# Sheet1.net
KiCad netlist of a schematic drawn in Altium Designer
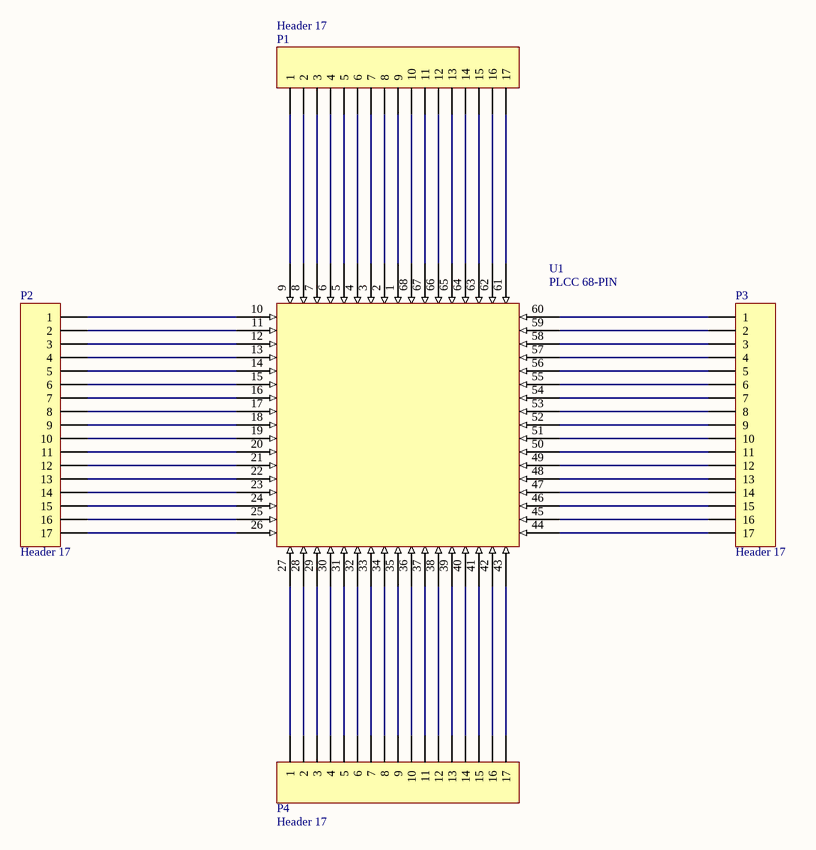
[diagram p0: Sheet1.SchDoc]

(export (version "E")
  (design (tool "Eeschema 10.0.6"))
  (components
    (comp (ref "P1")
      (value "Header 17")
      (footprint "HDR1X17")
      (description "Header, 17-Pin")
      (fields (field (name "PUBLISHER") "Altium Limited"))
      (libsource (lib "") (part "Header 17_3"))
    )
    (comp (ref "P2")
      (value "Header 17")
      (footprint "HDR1X17")
      (description "Header, 17-Pin")
      (fields (field (name "PUBLISHER") "Altium Limited"))
      (libsource (lib "Miscellaneous Connectors") (part "Header 17"))
    )
    (comp (ref "P3")
      (value "Header 17")
      (footprint "HDR1X17")
      (description "Header, 17-Pin")
      (fields (field (name "PUBLISHER") "Altium Limited"))
      (libsource (lib "") (part "Header 17_2"))
    )
    (comp (ref "P4")
      (value "Header 17")
      (footprint "HDR1X17")
      (description "Header, 17-Pin")
      (fields (field (name "PUBLISHER") "Altium Limited"))
      (libsource (lib "") (part "Header 17_1"))
    )
    (comp (ref "U1")
      (value "PLCC 68-PIN")
      (footprint "PcbLib1:PLCC68")
      (description "Custom IC")
      (libsource (lib "Schlib1") (part "PLCC 68-PIN"))
    )
  )
  (nets
    (net (code "1") (name "Net-(P1-Pad1)") (class "Default")
      (node (ref "P1") (pin "1") (pinfunction "1_1") (pintype "passive"))
      (node (ref "U1") (pin "9") (pintype "input"))
    )
    (net (code "2") (name "Net-(P1-Pad2)") (class "Default")
      (node (ref "P1") (pin "2") (pinfunction "2_2") (pintype "passive"))
      (node (ref "U1") (pin "8") (pintype "input"))
    )
    (net (code "3") (name "Net-(P1-Pad3)") (class "Default")
      (node (ref "P1") (pin "3") (pinfunction "3_3") (pintype "passive"))
      (node (ref "U1") (pin "7") (pintype "input"))
    )
    (net (code "4") (name "Net-(P1-Pad4)") (class "Default")
      (node (ref "P1") (pin "4") (pinfunction "4_4") (pintype "passive"))
      (node (ref "U1") (pin "6") (pintype "input"))
    )
    (net (code "5") (name "Net-(P1-Pad5)") (class "Default")
      (node (ref "P1") (pin "5") (pinfunction "5_5") (pintype "passive"))
      (node (ref "U1") (pin "5") (pintype "input"))
    )
    (net (code "6") (name "Net-(P1-Pad6)") (class "Default")
      (node (ref "P1") (pin "6") (pinfunction "6_6") (pintype "passive"))
      (node (ref "U1") (pin "4") (pintype "input"))
    )
    (net (code "7") (name "Net-(P1-Pad7)") (class "Default")
      (node (ref "P1") (pin "7") (pinfunction "7_7") (pintype "passive"))
      (node (ref "U1") (pin "3") (pintype "input"))
    )
    (net (code "8") (name "Net-(P1-Pad8)") (class "Default")
      (node (ref "P1") (pin "8") (pinfunction "8_8") (pintype "passive"))
      (node (ref "U1") (pin "2") (pintype "input"))
    )
    (net (code "9") (name "Net-(P1-Pad9)") (class "Default")
      (node (ref "P1") (pin "9") (pinfunction "9_9") (pintype "passive"))
      (node (ref "U1") (pin "1") (pintype "input"))
    )
    (net (code "10") (name "Net-(P1-Pad10)") (class "Default")
      (node (ref "P1") (pin "10") (pinfunction "10_10") (pintype "passive"))
      (node (ref "U1") (pin "68") (pintype "input"))
    )
    (net (code "11") (name "Net-(P1-Pad11)") (class "Default")
      (node (ref "P1") (pin "11") (pinfunction "11_11") (pintype "passive"))
      (node (ref "U1") (pin "67") (pintype "input"))
    )
    (net (code "12") (name "Net-(P1-Pad12)") (class "Default")
      (node (ref "P1") (pin "12") (pinfunction "12_12") (pintype "passive"))
      (node (ref "U1") (pin "66") (pintype "input"))
    )
    (net (code "13") (name "Net-(P1-Pad13)") (class "Default")
      (node (ref "P1") (pin "13") (pinfunction "13_13") (pintype "passive"))
      (node (ref "U1") (pin "65") (pintype "input"))
    )
    (net (code "14") (name "Net-(P1-Pad14)") (class "Default")
      (node (ref "P1") (pin "14") (pinfunction "14_14") (pintype "passive"))
      (node (ref "U1") (pin "64") (pintype "input"))
    )
    (net (code "15") (name "Net-(P1-Pad15)") (class "Default")
      (node (ref "P1") (pin "15") (pinfunction "15_15") (pintype "passive"))
      (node (ref "U1") (pin "63") (pintype "input"))
    )
    (net (code "16") (name "Net-(P1-Pad16)") (class "Default")
      (node (ref "P1") (pin "16") (pinfunction "16_16") (pintype "passive"))
      (node (ref "U1") (pin "62") (pintype "input"))
    )
    (net (code "17") (name "Net-(P1-Pad17)") (class "Default")
      (node (ref "P1") (pin "17") (pinfunction "17_17") (pintype "passive"))
      (node (ref "U1") (pin "61") (pintype "input"))
    )
    (net (code "18") (name "Net-(P2-Pad1)") (class "Default")
      (node (ref "P2") (pin "1") (pinfunction "1_1") (pintype "passive"))
      (node (ref "U1") (pin "10") (pintype "input"))
    )
    (net (code "19") (name "Net-(P2-Pad2)") (class "Default")
      (node (ref "P2") (pin "2") (pinfunction "2_2") (pintype "passive"))
      (node (ref "U1") (pin "11") (pintype "input"))
    )
    (net (code "20") (name "Net-(P2-Pad3)") (class "Default")
      (node (ref "P2") (pin "3") (pinfunction "3_3") (pintype "passive"))
      (node (ref "U1") (pin "12") (pintype "input"))
    )
    (net (code "21") (name "Net-(P2-Pad4)") (class "Default")
      (node (ref "P2") (pin "4") (pinfunction "4_4") (pintype "passive"))
      (node (ref "U1") (pin "13") (pintype "input"))
    )
    (net (code "22") (name "Net-(P2-Pad5)") (class "Default")
      (node (ref "P2") (pin "5") (pinfunction "5_5") (pintype "passive"))
      (node (ref "U1") (pin "14") (pintype "input"))
    )
    (net (code "23") (name "Net-(P2-Pad6)") (class "Default")
      (node (ref "P2") (pin "6") (pinfunction "6_6") (pintype "passive"))
      (node (ref "U1") (pin "15") (pintype "input"))
    )
    (net (code "24") (name "Net-(P2-Pad7)") (class "Default")
      (node (ref "P2") (pin "7") (pinfunction "7_7") (pintype "passive"))
      (node (ref "U1") (pin "16") (pintype "input"))
    )
    (net (code "25") (name "Net-(P2-Pad8)") (class "Default")
      (node (ref "P2") (pin "8") (pinfunction "8_8") (pintype "passive"))
      (node (ref "U1") (pin "17") (pintype "input"))
    )
    (net (code "26") (name "Net-(P2-Pad9)") (class "Default")
      (node (ref "P2") (pin "9") (pinfunction "9_9") (pintype "passive"))
      (node (ref "U1") (pin "18") (pintype "input"))
    )
    (net (code "27") (name "Net-(P2-Pad10)") (class "Default")
      (node (ref "P2") (pin "10") (pinfunction "10_10") (pintype "passive"))
      (node (ref "U1") (pin "19") (pintype "input"))
    )
    (net (code "28") (name "Net-(P2-Pad11)") (class "Default")
      (node (ref "P2") (pin "11") (pinfunction "11_11") (pintype "passive"))
      (node (ref "U1") (pin "20") (pintype "input"))
    )
    (net (code "29") (name "Net-(P2-Pad12)") (class "Default")
      (node (ref "P2") (pin "12") (pinfunction "12_12") (pintype "passive"))
      (node (ref "U1") (pin "21") (pintype "input"))
    )
    (net (code "30") (name "Net-(P2-Pad13)") (class "Default")
      (node (ref "P2") (pin "13") (pinfunction "13_13") (pintype "passive"))
      (node (ref "U1") (pin "22") (pintype "input"))
    )
    (net (code "31") (name "Net-(P2-Pad14)") (class "Default")
      (node (ref "P2") (pin "14") (pinfunction "14_14") (pintype "passive"))
      (node (ref "U1") (pin "23") (pintype "input"))
    )
    (net (code "32") (name "Net-(P2-Pad15)") (class "Default")
      (node (ref "P2") (pin "15") (pinfunction "15_15") (pintype "passive"))
      (node (ref "U1") (pin "24") (pintype "input"))
    )
    (net (code "33") (name "Net-(P2-Pad16)") (class "Default")
      (node (ref "P2") (pin "16") (pinfunction "16_16") (pintype "passive"))
      (node (ref "U1") (pin "25") (pintype "input"))
    )
    (net (code "34") (name "Net-(P2-Pad17)") (class "Default")
      (node (ref "P2") (pin "17") (pinfunction "17_17") (pintype "passive"))
      (node (ref "U1") (pin "26") (pintype "input"))
    )
    (net (code "35") (name "Net-(P3-Pad1)") (class "Default")
      (node (ref "P3") (pin "1") (pinfunction "1_1") (pintype "passive"))
      (node (ref "U1") (pin "60") (pintype "input"))
    )
    (net (code "36") (name "Net-(P3-Pad2)") (class "Default")
      (node (ref "P3") (pin "2") (pinfunction "2_2") (pintype "passive"))
      (node (ref "U1") (pin "59") (pintype "input"))
    )
    (net (code "37") (name "Net-(P3-Pad3)") (class "Default")
      (node (ref "P3") (pin "3") (pinfunction "3_3") (pintype "passive"))
      (node (ref "U1") (pin "58") (pintype "input"))
    )
    (net (code "38") (name "Net-(P3-Pad4)") (class "Default")
      (node (ref "P3") (pin "4") (pinfunction "4_4") (pintype "passive"))
      (node (ref "U1") (pin "57") (pintype "input"))
    )
    (net (code "39") (name "Net-(P3-Pad5)") (class "Default")
      (node (ref "P3") (pin "5") (pinfunction "5_5") (pintype "passive"))
      (node (ref "U1") (pin "56") (pintype "input"))
    )
    (net (code "40") (name "Net-(P3-Pad6)") (class "Default")
      (node (ref "P3") (pin "6") (pinfunction "6_6") (pintype "passive"))
      (node (ref "U1") (pin "55") (pintype "input"))
    )
    (net (code "41") (name "Net-(P3-Pad7)") (class "Default")
      (node (ref "P3") (pin "7") (pinfunction "7_7") (pintype "passive"))
      (node (ref "U1") (pin "54") (pintype "input"))
    )
    (net (code "42") (name "Net-(P3-Pad8)") (class "Default")
      (node (ref "P3") (pin "8") (pinfunction "8_8") (pintype "passive"))
      (node (ref "U1") (pin "53") (pintype "input"))
    )
    (net (code "43") (name "Net-(P3-Pad9)") (class "Default")
      (node (ref "P3") (pin "9") (pinfunction "9_9") (pintype "passive"))
      (node (ref "U1") (pin "52") (pintype "input"))
    )
    (net (code "44") (name "Net-(P3-Pad10)") (class "Default")
      (node (ref "P3") (pin "10") (pinfunction "10_10") (pintype "passive"))
      (node (ref "U1") (pin "51") (pintype "input"))
    )
    (net (code "45") (name "Net-(P3-Pad11)") (class "Default")
      (node (ref "P3") (pin "11") (pinfunction "11_11") (pintype "passive"))
      (node (ref "U1") (pin "50") (pintype "input"))
    )
    (net (code "46") (name "Net-(P3-Pad12)") (class "Default")
      (node (ref "P3") (pin "12") (pinfunction "12_12") (pintype "passive"))
      (node (ref "U1") (pin "49") (pintype "input"))
    )
    (net (code "47") (name "Net-(P3-Pad13)") (class "Default")
      (node (ref "P3") (pin "13") (pinfunction "13_13") (pintype "passive"))
      (node (ref "U1") (pin "48") (pintype "input"))
    )
    (net (code "48") (name "Net-(P3-Pad14)") (class "Default")
      (node (ref "P3") (pin "14") (pinfunction "14_14") (pintype "passive"))
      (node (ref "U1") (pin "47") (pintype "input"))
    )
    (net (code "49") (name "Net-(P3-Pad15)") (class "Default")
      (node (ref "P3") (pin "15") (pinfunction "15_15") (pintype "passive"))
      (node (ref "U1") (pin "46") (pintype "input"))
    )
    (net (code "50") (name "Net-(P3-Pad16)") (class "Default")
      (node (ref "P3") (pin "16") (pinfunction "16_16") (pintype "passive"))
      (node (ref "U1") (pin "45") (pintype "input"))
    )
    (net (code "51") (name "Net-(P3-Pad17)") (class "Default")
      (node (ref "P3") (pin "17") (pinfunction "17_17") (pintype "passive"))
      (node (ref "U1") (pin "44") (pintype "input"))
    )
    (net (code "52") (name "Net-(P4-Pad1)") (class "Default")
      (node (ref "P4") (pin "1") (pinfunction "1_1") (pintype "passive"))
      (node (ref "U1") (pin "27") (pintype "input"))
    )
    (net (code "53") (name "Net-(P4-Pad2)") (class "Default")
      (node (ref "P4") (pin "2") (pinfunction "2_2") (pintype "passive"))
      (node (ref "U1") (pin "28") (pintype "input"))
    )
    (net (code "54") (name "Net-(P4-Pad3)") (class "Default")
      (node (ref "P4") (pin "3") (pinfunction "3_3") (pintype "passive"))
      (node (ref "U1") (pin "29") (pintype "input"))
    )
    (net (code "55") (name "Net-(P4-Pad4)") (class "Default")
      (node (ref "P4") (pin "4") (pinfunction "4_4") (pintype "passive"))
      (node (ref "U1") (pin "30") (pintype "input"))
    )
    (net (code "56") (name "Net-(P4-Pad5)") (class "Default")
      (node (ref "P4") (pin "5") (pinfunction "5_5") (pintype "passive"))
      (node (ref "U1") (pin "31") (pintype "input"))
    )
    (net (code "57") (name "Net-(P4-Pad6)") (class "Default")
      (node (ref "P4") (pin "6") (pinfunction "6_6") (pintype "passive"))
      (node (ref "U1") (pin "32") (pintype "input"))
    )
    (net (code "58") (name "Net-(P4-Pad7)") (class "Default")
      (node (ref "P4") (pin "7") (pinfunction "7_7") (pintype "passive"))
      (node (ref "U1") (pin "33") (pintype "input"))
    )
    (net (code "59") (name "Net-(P4-Pad8)") (class "Default")
      (node (ref "P4") (pin "8") (pinfunction "8_8") (pintype "passive"))
      (node (ref "U1") (pin "34") (pintype "input"))
    )
    (net (code "60") (name "Net-(P4-Pad9)") (class "Default")
      (node (ref "P4") (pin "9") (pinfunction "9_9") (pintype "passive"))
      (node (ref "U1") (pin "35") (pintype "input"))
    )
    (net (code "61") (name "Net-(P4-Pad10)") (class "Default")
      (node (ref "P4") (pin "10") (pinfunction "10_10") (pintype "passive"))
      (node (ref "U1") (pin "36") (pintype "input"))
    )
    (net (code "62") (name "Net-(P4-Pad11)") (class "Default")
      (node (ref "P4") (pin "11") (pinfunction "11_11") (pintype "passive"))
      (node (ref "U1") (pin "37") (pintype "input"))
    )
    (net (code "63") (name "Net-(P4-Pad12)") (class "Default")
      (node (ref "P4") (pin "12") (pinfunction "12_12") (pintype "passive"))
      (node (ref "U1") (pin "38") (pintype "input"))
    )
    (net (code "64") (name "Net-(P4-Pad13)") (class "Default")
      (node (ref "P4") (pin "13") (pinfunction "13_13") (pintype "passive"))
      (node (ref "U1") (pin "39") (pintype "input"))
    )
    (net (code "65") (name "Net-(P4-Pad14)") (class "Default")
      (node (ref "P4") (pin "14") (pinfunction "14_14") (pintype "passive"))
      (node (ref "U1") (pin "40") (pintype "input"))
    )
    (net (code "66") (name "Net-(P4-Pad15)") (class "Default")
      (node (ref "P4") (pin "15") (pinfunction "15_15") (pintype "passive"))
      (node (ref "U1") (pin "41") (pintype "input"))
    )
    (net (code "67") (name "Net-(P4-Pad16)") (class "Default")
      (node (ref "P4") (pin "16") (pinfunction "16_16") (pintype "passive"))
      (node (ref "U1") (pin "42") (pintype "input"))
    )
    (net (code "68") (name "Net-(P4-Pad17)") (class "Default")
      (node (ref "P4") (pin "17") (pinfunction "17_17") (pintype "passive"))
      (node (ref "U1") (pin "43") (pintype "input"))
    )
  )
)
